# 2_MCU.net
KiCad netlist of a schematic drawn in Altium Designer
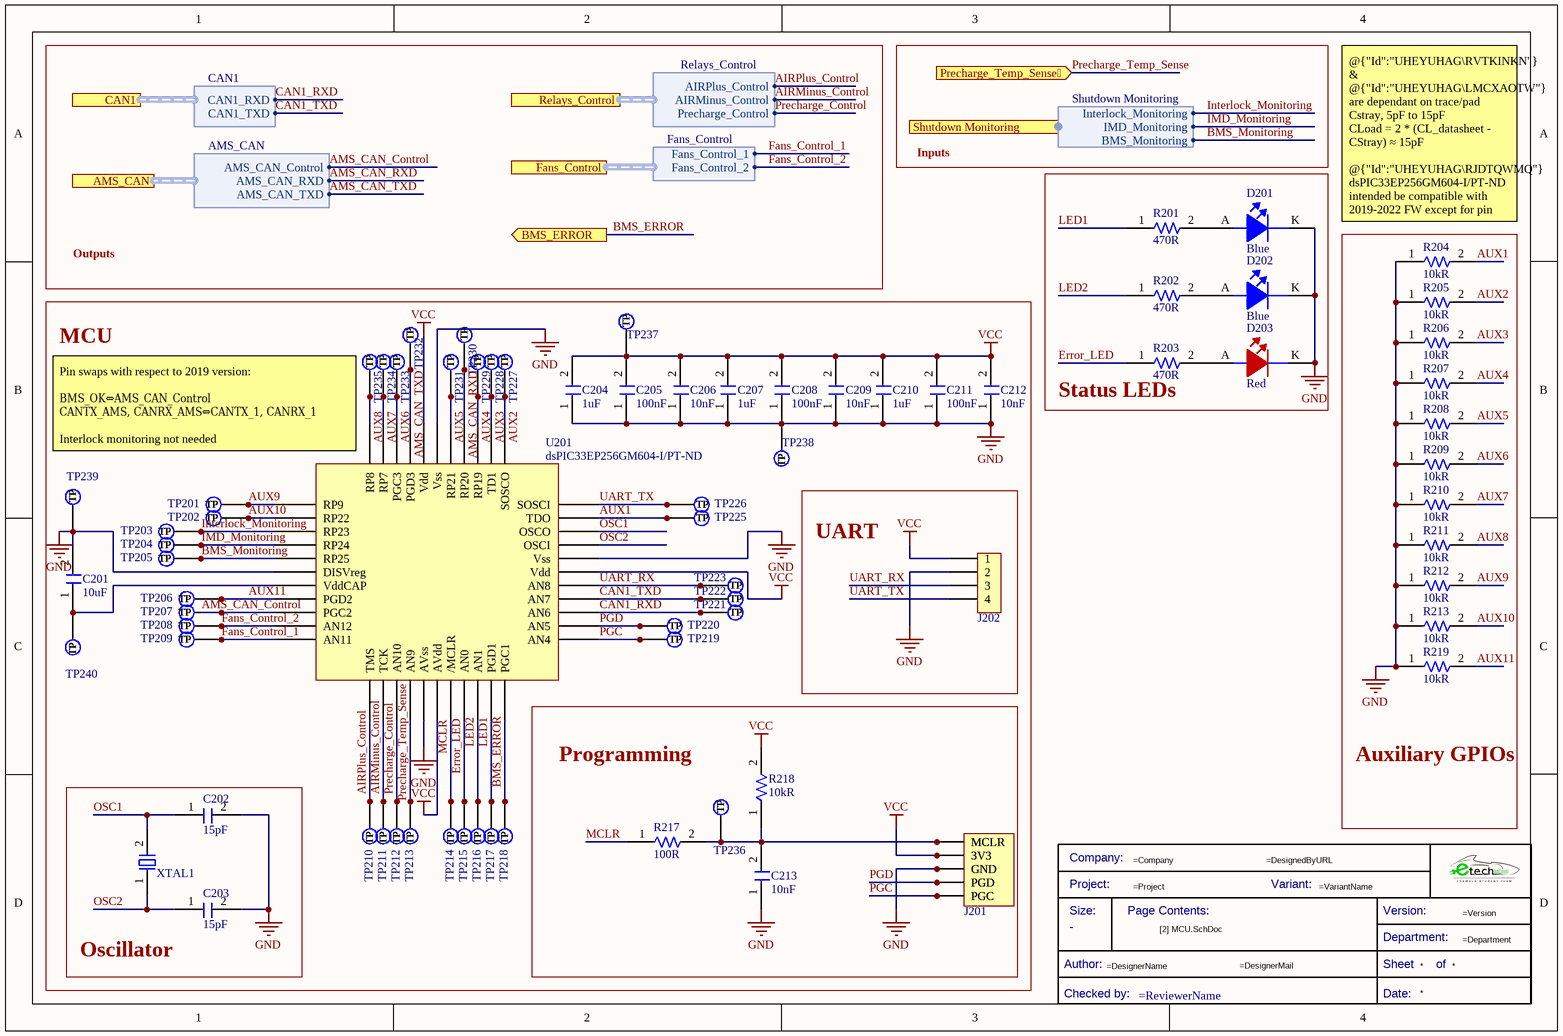
[diagram p0: [2] MCU.SchDoc]

(export (version "E")
  (design (tool "Eeschema 10.0.6"))
  (components
    (comp (ref "*")
      (value "Title Block_template")
      (description "Standard Title Block")
      (fields (field (name "SIZE") "-"))
      (libsource (lib "e-Tech_Racing") (part "Title Block_template"))
    )
    (comp (ref "C201")
      (value "885012208018")
      (footprint "C1206FNPC-RW")
      (description "Cap, 10ΜF, 10V, 10%, X7R, 1206")
      (fields
        (field (name "TOLERANCE") "10%")
        (field (name "CAPACITANCE") "10uF")
        (field (name ".CREATOR") "GP")
      )
      (libsource (lib "Passives") (part "C10u-10V-1206FNPC-X7R"))
    )
    (comp (ref "C202")
      (value "885012007052")
      (footprint "C0805FNPC-R")
      (description "Cap, 15PF, 50V, 5%, C0G/NP0, 0805")
      (fields
        (field (name "TOLERANCE") "5%")
        (field (name "CAPACITANCE") "15pF")
        (field (name ".CREATOR") "DR")
      )
      (libsource (lib "Passives") (part "C15p-50V-0805FNPC-NP0"))
    )
    (comp (ref "C203")
      (value "885012007052")
      (footprint "C0805FNPC-R")
      (description "Cap, 15PF, 50V, 5%, C0G/NP0, 0805")
      (fields
        (field (name "TOLERANCE") "5%")
        (field (name "CAPACITANCE") "15pF")
        (field (name ".CREATOR") "DR")
      )
      (libsource (lib "Passives") (part "C15p-50V-0805FNPC-NP0"))
    )
    (comp (ref "C204")
      (value "885012207103")
      (footprint "C0805FNPC-R")
      (fields
        (field (name "TOLERANCE") "10%")
        (field (name "CAPACITANCE") "1uF")
        (field (name ".CREATOR") "GP")
      )
      (libsource (lib "Passives") (part "C1u-50V-0805FNPC-X7R"))
    )
    (comp (ref "C205")
      (value "885012207098")
      (footprint "C0805FNPC-R")
      (description "Cap, 0.1ΜF, 50V, 10%, X7R, 0805")
      (fields
        (field (name "TOLERANCE") "10%")
        (field (name "CAPACITANCE") "100nF")
        (field (name ".CREATOR") "DR")
      )
      (libsource (lib "Passives") (part "C100n-50V-0805FNPC-X7R"))
    )
    (comp (ref "C206")
      (value "885012207092")
      (footprint "C0805FNPC-R")
      (description "Cap, 0.01ΜF, 50V, 10%, X7R, 0805")
      (fields
        (field (name "TOLERANCE") "10%")
        (field (name "CAPACITANCE") "10nF")
        (field (name ".CREATOR") "DR")
      )
      (libsource (lib "Passives") (part "C10n-50V-0805FNPC-X7R"))
    )
    (comp (ref "C207")
      (value "885012207103")
      (footprint "C0805FNPC-R")
      (fields
        (field (name "TOLERANCE") "10%")
        (field (name "CAPACITANCE") "1uF")
        (field (name ".CREATOR") "GP")
      )
      (libsource (lib "Passives") (part "C1u-50V-0805FNPC-X7R"))
    )
    (comp (ref "C208")
      (value "885012207098")
      (footprint "C0805FNPC-R")
      (description "Cap, 0.1ΜF, 50V, 10%, X7R, 0805")
      (fields
        (field (name "TOLERANCE") "10%")
        (field (name "CAPACITANCE") "100nF")
        (field (name ".CREATOR") "DR")
      )
      (libsource (lib "Passives") (part "C100n-50V-0805FNPC-X7R"))
    )
    (comp (ref "C209")
      (value "885012207092")
      (footprint "C0805FNPC-R")
      (description "Cap, 0.01ΜF, 50V, 10%, X7R, 0805")
      (fields
        (field (name "TOLERANCE") "10%")
        (field (name "CAPACITANCE") "10nF")
        (field (name ".CREATOR") "DR")
      )
      (libsource (lib "Passives") (part "C10n-50V-0805FNPC-X7R"))
    )
    (comp (ref "C210")
      (value "885012207103")
      (footprint "C0805FNPC-R")
      (fields
        (field (name "TOLERANCE") "10%")
        (field (name "CAPACITANCE") "1uF")
        (field (name ".CREATOR") "GP")
      )
      (libsource (lib "Passives") (part "C1u-50V-0805FNPC-X7R"))
    )
    (comp (ref "C211")
      (value "885012207098")
      (footprint "C0805FNPC-R")
      (description "Cap, 0.1ΜF, 50V, 10%, X7R, 0805")
      (fields
        (field (name "TOLERANCE") "10%")
        (field (name "CAPACITANCE") "100nF")
        (field (name ".CREATOR") "DR")
      )
      (libsource (lib "Passives") (part "C100n-50V-0805FNPC-X7R"))
    )
    (comp (ref "C212")
      (value "885012207092")
      (footprint "C0805FNPC-R")
      (description "Cap, 0.01ΜF, 50V, 10%, X7R, 0805")
      (fields
        (field (name "TOLERANCE") "10%")
        (field (name "CAPACITANCE") "10nF")
        (field (name ".CREATOR") "DR")
      )
      (libsource (lib "Passives") (part "C10n-50V-0805FNPC-X7R"))
    )
    (comp (ref "C213")
      (value "885012207092")
      (footprint "C0805FNPC-R")
      (description "Cap, 0.01ΜF, 50V, 10%, X7R, 0805")
      (fields
        (field (name "TOLERANCE") "10%")
        (field (name "CAPACITANCE") "10nF")
        (field (name ".CREATOR") "DR")
      )
      (libsource (lib "Passives") (part "C10n-50V-0805FNPC-X7R"))
    )
    (comp (ref "D201")
      (value "150080BS75000")
      (footprint "LED_0805_WE")
      (description "LED BLUE CLEAR 0805 SMD")
      (fields (field (name "COLOR") "Blue") (field (name ".CREATOR") "GP"))
      (libsource (lib "Semiconductor") (part "LEDBS-0805-145"))
    )
    (comp (ref "D202")
      (value "150080BS75000")
      (footprint "LED_0805_WE")
      (description "LED BLUE CLEAR 0805 SMD")
      (fields (field (name "COLOR") "Blue") (field (name ".CREATOR") "GP"))
      (libsource (lib "Semiconductor") (part "LEDBS-0805-145"))
    )
    (comp (ref "D203")
      (value "150080RS75000")
      (footprint "LED_0805_WE")
      (description "0805(H=0.8mm) 红色 高亮 λD=625nm VF=2V IF=30mA PD=72mW")
      (fields (field (name "COLOR") "Red") (field (name ".CREATOR") "DR"))
      (libsource (lib "Semiconductor") (part "LEDRS-0805-150"))
    )
    (comp (ref "J201")
      (value "61300511121")
      (footprint "J_PinHeader_1x5")
      (description "THT Vertical Pin Header WR-PHD, Pitch 2.54 mm, Single Row, 5 pins")
      (fields (field (name "MANUFACTURER") "Molex") (field (name ".CREATOR") "GP"))
      (libsource (lib "Electromechanical") (part "J_Pickit3"))
    )
    (comp (ref "J202")
      (value "61300411121")
      (footprint "J_PinHeader_1x4")
      (description "CONN HEADER 4 POS 2.54")
      (fields (field (name ".CREATOR") "AC"))
      (libsource (lib "Electromechanical") (part "J_UART"))
    )
    (comp (ref "R201")
      (value "CR0805-FX-4700GLF")
      (footprint "R0805FTK")
      (description "Res Thick Film 0805 470 Ohm 1% 1/8W ±100ppm/°C Molded SMD SMD Paper Tape on Plastic Reel")
      (fields
        (field (name "TOLERANCE") "1%")
        (field (name "RESISTANCE") "470R")
        (field (name ".CREATOR") "DR")
      )
      (libsource (lib "Passives") (part "R470-0805FTK"))
    )
    (comp (ref "R202")
      (value "CR0805-FX-4700GLF")
      (footprint "R0805FTK")
      (description "Res Thick Film 0805 470 Ohm 1% 1/8W ±100ppm/°C Molded SMD SMD Paper Tape on Plastic Reel")
      (fields
        (field (name "TOLERANCE") "1%")
        (field (name "RESISTANCE") "470R")
        (field (name ".CREATOR") "DR")
      )
      (libsource (lib "Passives") (part "R470-0805FTK"))
    )
    (comp (ref "R203")
      (value "CR0805-FX-4700GLF")
      (footprint "R0805FTK")
      (description "Res Thick Film 0805 470 Ohm 1% 1/8W ±100ppm/°C Molded SMD SMD Paper Tape on Plastic Reel")
      (fields
        (field (name "TOLERANCE") "1%")
        (field (name "RESISTANCE") "470R")
        (field (name ".CREATOR") "DR")
      )
      (libsource (lib "Passives") (part "R470-0805FTK"))
    )
    (comp (ref "R204")
      (value "CR0805-JW-103ELF")
      (footprint "R0805FTK")
      (fields
        (field (name "TOLERANCE") "5%")
        (field (name "RESISTANCE") "10kR")
        (field (name ".CREATOR") "DR")
      )
      (libsource (lib "Passives") (part "R10k-0805FTK"))
    )
    (comp (ref "R205")
      (value "CR0805-JW-103ELF")
      (footprint "R0805FTK")
      (fields
        (field (name "TOLERANCE") "5%")
        (field (name "RESISTANCE") "10kR")
        (field (name ".CREATOR") "DR")
      )
      (libsource (lib "Passives") (part "R10k-0805FTK"))
    )
    (comp (ref "R206")
      (value "CR0805-JW-103ELF")
      (footprint "R0805FTK")
      (fields
        (field (name "TOLERANCE") "5%")
        (field (name "RESISTANCE") "10kR")
        (field (name ".CREATOR") "DR")
      )
      (libsource (lib "Passives") (part "R10k-0805FTK"))
    )
    (comp (ref "R207")
      (value "CR0805-JW-103ELF")
      (footprint "R0805FTK")
      (fields
        (field (name "TOLERANCE") "5%")
        (field (name "RESISTANCE") "10kR")
        (field (name ".CREATOR") "DR")
      )
      (libsource (lib "Passives") (part "R10k-0805FTK"))
    )
    (comp (ref "R208")
      (value "CR0805-JW-103ELF")
      (footprint "R0805FTK")
      (fields
        (field (name "TOLERANCE") "5%")
        (field (name "RESISTANCE") "10kR")
        (field (name ".CREATOR") "DR")
      )
      (libsource (lib "Passives") (part "R10k-0805FTK"))
    )
    (comp (ref "R209")
      (value "CR0805-JW-103ELF")
      (footprint "R0805FTK")
      (fields
        (field (name "TOLERANCE") "5%")
        (field (name "RESISTANCE") "10kR")
        (field (name ".CREATOR") "DR")
      )
      (libsource (lib "Passives") (part "R10k-0805FTK"))
    )
    (comp (ref "R210")
      (value "CR0805-JW-103ELF")
      (footprint "R0805FTK")
      (fields
        (field (name "TOLERANCE") "5%")
        (field (name "RESISTANCE") "10kR")
        (field (name ".CREATOR") "DR")
      )
      (libsource (lib "Passives") (part "R10k-0805FTK"))
    )
    (comp (ref "R211")
      (value "CR0805-JW-103ELF")
      (footprint "R0805FTK")
      (fields
        (field (name "TOLERANCE") "5%")
        (field (name "RESISTANCE") "10kR")
        (field (name ".CREATOR") "DR")
      )
      (libsource (lib "Passives") (part "R10k-0805FTK"))
    )
    (comp (ref "R212")
      (value "CR0805-JW-103ELF")
      (footprint "R0805FTK")
      (fields
        (field (name "TOLERANCE") "5%")
        (field (name "RESISTANCE") "10kR")
        (field (name ".CREATOR") "DR")
      )
      (libsource (lib "Passives") (part "R10k-0805FTK"))
    )
    (comp (ref "R213")
      (value "CR0805-JW-103ELF")
      (footprint "R0805FTK")
      (fields
        (field (name "TOLERANCE") "5%")
        (field (name "RESISTANCE") "10kR")
        (field (name ".CREATOR") "DR")
      )
      (libsource (lib "Passives") (part "R10k-0805FTK"))
    )
    (comp (ref "R217")
      (value "CR0805-FX-1000ELF")
      (footprint "R0805FTK")
      (description "Res Thick Film 0805 100 Ohm 1% 1/8W ±100ppm/°C Molded SMD SMD Paper Tape on Plastic Reel")
      (fields
        (field (name "TOLERANCE") "1%")
        (field (name "RESISTANCE") "100R")
        (field (name ".CREATOR") "DR")
      )
      (libsource (lib "Passives") (part "R100-0805FTK"))
    )
    (comp (ref "R218")
      (value "CR0805-JW-103ELF")
      (footprint "R0805FTK")
      (fields
        (field (name "TOLERANCE") "5%")
        (field (name "RESISTANCE") "10kR")
        (field (name ".CREATOR") "DR")
      )
      (libsource (lib "Passives") (part "R10k-0805FTK"))
    )
    (comp (ref "R219")
      (value "CR0805-JW-103ELF")
      (footprint "R0805FTK")
      (fields
        (field (name "TOLERANCE") "5%")
        (field (name "RESISTANCE") "10kR")
        (field (name ".CREATOR") "DR")
      )
      (libsource (lib "Passives") (part "R10k-0805FTK"))
    )
    (comp (ref "TP201")
      (value "TestPoint")
      (footprint "TestPoint")
      (description "Test Point 1x1 mm")
      (fields (field (name ".CREATOR") "GP") (field (name ".PCBCHECK") "GP") (field (name ".SCHCHECK") "GP"))
      (libsource (lib "e-Tech_Racing") (part "TestPoint"))
    )
    (comp (ref "TP202")
      (value "TestPoint")
      (footprint "TestPoint")
      (description "Test Point 1x1 mm")
      (fields (field (name ".CREATOR") "GP") (field (name ".PCBCHECK") "GP") (field (name ".SCHCHECK") "GP"))
      (libsource (lib "e-Tech_Racing") (part "TestPoint"))
    )
    (comp (ref "TP203")
      (value "TestPoint")
      (footprint "TestPoint")
      (description "Test Point 1x1 mm")
      (fields (field (name ".CREATOR") "GP") (field (name ".PCBCHECK") "GP") (field (name ".SCHCHECK") "GP"))
      (libsource (lib "e-Tech_Racing") (part "TestPoint"))
    )
    (comp (ref "TP204")
      (value "TestPoint")
      (footprint "TestPoint")
      (description "Test Point 1x1 mm")
      (fields (field (name ".CREATOR") "GP") (field (name ".PCBCHECK") "GP") (field (name ".SCHCHECK") "GP"))
      (libsource (lib "e-Tech_Racing") (part "TestPoint"))
    )
    (comp (ref "TP205")
      (value "TestPoint")
      (footprint "TestPoint")
      (description "Test Point 1x1 mm")
      (fields (field (name ".CREATOR") "GP") (field (name ".PCBCHECK") "GP") (field (name ".SCHCHECK") "GP"))
      (libsource (lib "e-Tech_Racing") (part "TestPoint"))
    )
    (comp (ref "TP206")
      (value "TestPoint")
      (footprint "TestPoint")
      (description "Test Point 1x1 mm")
      (fields (field (name ".CREATOR") "GP") (field (name ".PCBCHECK") "GP") (field (name ".SCHCHECK") "GP"))
      (libsource (lib "e-Tech_Racing") (part "TestPoint"))
    )
    (comp (ref "TP207")
      (value "TestPoint")
      (footprint "TestPoint")
      (description "Test Point 1x1 mm")
      (fields (field (name ".CREATOR") "GP") (field (name ".PCBCHECK") "GP") (field (name ".SCHCHECK") "GP"))
      (libsource (lib "e-Tech_Racing") (part "TestPoint"))
    )
    (comp (ref "TP208")
      (value "TestPoint")
      (footprint "TestPoint")
      (description "Test Point 1x1 mm")
      (fields (field (name ".CREATOR") "GP") (field (name ".PCBCHECK") "GP") (field (name ".SCHCHECK") "GP"))
      (libsource (lib "e-Tech_Racing") (part "TestPoint"))
    )
    (comp (ref "TP209")
      (value "TestPoint")
      (footprint "TestPoint")
      (description "Test Point 1x1 mm")
      (fields (field (name ".CREATOR") "GP") (field (name ".PCBCHECK") "GP") (field (name ".SCHCHECK") "GP"))
      (libsource (lib "e-Tech_Racing") (part "TestPoint"))
    )
    (comp (ref "TP210")
      (value "TestPoint")
      (footprint "TestPoint")
      (description "Test Point 1x1 mm")
      (fields (field (name ".CREATOR") "GP") (field (name ".PCBCHECK") "GP") (field (name ".SCHCHECK") "GP"))
      (libsource (lib "e-Tech_Racing") (part "TestPoint"))
    )
    (comp (ref "TP211")
      (value "TestPoint")
      (footprint "TestPoint")
      (description "Test Point 1x1 mm")
      (fields (field (name ".CREATOR") "GP") (field (name ".PCBCHECK") "GP") (field (name ".SCHCHECK") "GP"))
      (libsource (lib "e-Tech_Racing") (part "TestPoint"))
    )
    (comp (ref "TP212")
      (value "TestPoint")
      (footprint "TestPoint")
      (description "Test Point 1x1 mm")
      (fields (field (name ".CREATOR") "GP") (field (name ".PCBCHECK") "GP") (field (name ".SCHCHECK") "GP"))
      (libsource (lib "e-Tech_Racing") (part "TestPoint"))
    )
    (comp (ref "TP213")
      (value "TestPoint")
      (footprint "TestPoint")
      (description "Test Point 1x1 mm")
      (fields (field (name ".CREATOR") "GP") (field (name ".PCBCHECK") "GP") (field (name ".SCHCHECK") "GP"))
      (libsource (lib "e-Tech_Racing") (part "TestPoint"))
    )
    (comp (ref "TP214")
      (value "TestPoint")
      (footprint "TestPoint")
      (description "Test Point 1x1 mm")
      (fields (field (name ".CREATOR") "GP") (field (name ".PCBCHECK") "GP") (field (name ".SCHCHECK") "GP"))
      (libsource (lib "e-Tech_Racing") (part "TestPoint"))
    )
    (comp (ref "TP215")
      (value "TestPoint")
      (footprint "TestPoint")
      (description "Test Point 1x1 mm")
      (fields (field (name ".CREATOR") "GP") (field (name ".PCBCHECK") "GP") (field (name ".SCHCHECK") "GP"))
      (libsource (lib "e-Tech_Racing") (part "TestPoint"))
    )
    (comp (ref "TP216")
      (value "TestPoint")
      (footprint "TestPoint")
      (description "Test Point 1x1 mm")
      (fields (field (name ".CREATOR") "GP") (field (name ".PCBCHECK") "GP") (field (name ".SCHCHECK") "GP"))
      (libsource (lib "e-Tech_Racing") (part "TestPoint"))
    )
    (comp (ref "TP217")
      (value "TestPoint")
      (footprint "TestPoint")
      (description "Test Point 1x1 mm")
      (fields (field (name ".CREATOR") "GP") (field (name ".PCBCHECK") "GP") (field (name ".SCHCHECK") "GP"))
      (libsource (lib "e-Tech_Racing") (part "TestPoint"))
    )
    (comp (ref "TP218")
      (value "TestPoint")
      (footprint "TestPoint")
      (description "Test Point 1x1 mm")
      (fields (field (name ".CREATOR") "GP") (field (name ".PCBCHECK") "GP") (field (name ".SCHCHECK") "GP"))
      (libsource (lib "e-Tech_Racing") (part "TestPoint"))
    )
    (comp (ref "TP219")
      (value "TestPoint")
      (footprint "TestPoint")
      (description "Test Point 1x1 mm")
      (fields (field (name ".CREATOR") "GP") (field (name ".PCBCHECK") "GP") (field (name ".SCHCHECK") "GP"))
      (libsource (lib "e-Tech_Racing") (part "TestPoint"))
    )
    (comp (ref "TP220")
      (value "TestPoint")
      (footprint "TestPoint")
      (description "Test Point 1x1 mm")
      (fields (field (name ".CREATOR") "GP") (field (name ".PCBCHECK") "GP") (field (name ".SCHCHECK") "GP"))
      (libsource (lib "e-Tech_Racing") (part "TestPoint"))
    )
    (comp (ref "TP221")
      (value "TestPoint")
      (footprint "TestPoint")
      (description "Test Point 1x1 mm")
      (fields (field (name ".CREATOR") "GP") (field (name ".PCBCHECK") "GP") (field (name ".SCHCHECK") "GP"))
      (libsource (lib "e-Tech_Racing") (part "TestPoint"))
    )
    (comp (ref "TP222")
      (value "TestPoint")
      (footprint "TestPoint")
      (description "Test Point 1x1 mm")
      (fields (field (name ".CREATOR") "GP") (field (name ".PCBCHECK") "GP") (field (name ".SCHCHECK") "GP"))
      (libsource (lib "e-Tech_Racing") (part "TestPoint"))
    )
    (comp (ref "TP223")
      (value "TestPoint")
      (footprint "TestPoint")
      (description "Test Point 1x1 mm")
      (fields (field (name ".CREATOR") "GP") (field (name ".PCBCHECK") "GP") (field (name ".SCHCHECK") "GP"))
      (libsource (lib "e-Tech_Racing") (part "TestPoint"))
    )
    (comp (ref "TP225")
      (value "TestPoint")
      (footprint "TestPoint")
      (description "Test Point 1x1 mm")
      (fields (field (name ".CREATOR") "GP") (field (name ".PCBCHECK") "GP") (field (name ".SCHCHECK") "GP"))
      (libsource (lib "e-Tech_Racing") (part "TestPoint"))
    )
    (comp (ref "TP226")
      (value "TestPoint")
      (footprint "TestPoint")
      (description "Test Point 1x1 mm")
      (fields (field (name ".CREATOR") "GP") (field (name ".PCBCHECK") "GP") (field (name ".SCHCHECK") "GP"))
      (libsource (lib "e-Tech_Racing") (part "TestPoint"))
    )
    (comp (ref "TP227")
      (value "TestPoint")
      (footprint "TestPoint")
      (description "Test Point 1x1 mm")
      (fields (field (name ".CREATOR") "GP") (field (name ".PCBCHECK") "GP") (field (name ".SCHCHECK") "GP"))
      (libsource (lib "e-Tech_Racing") (part "TestPoint"))
    )
    (comp (ref "TP228")
      (value "TestPoint")
      (footprint "TestPoint")
      (description "Test Point 1x1 mm")
      (fields (field (name ".CREATOR") "GP") (field (name ".PCBCHECK") "GP") (field (name ".SCHCHECK") "GP"))
      (libsource (lib "e-Tech_Racing") (part "TestPoint"))
    )
    (comp (ref "TP229")
      (value "TestPoint")
      (footprint "TestPoint")
      (description "Test Point 1x1 mm")
      (fields (field (name ".CREATOR") "GP") (field (name ".PCBCHECK") "GP") (field (name ".SCHCHECK") "GP"))
      (libsource (lib "e-Tech_Racing") (part "TestPoint"))
    )
    (comp (ref "TP230")
      (value "TestPoint")
      (footprint "TestPoint")
      (description "Test Point 1x1 mm")
      (fields (field (name ".CREATOR") "GP") (field (name ".PCBCHECK") "GP") (field (name ".SCHCHECK") "GP"))
      (libsource (lib "e-Tech_Racing") (part "TestPoint"))
    )
    (comp (ref "TP231")
      (value "TestPoint")
      (footprint "TestPoint")
      (description "Test Point 1x1 mm")
      (fields (field (name ".CREATOR") "GP") (field (name ".PCBCHECK") "GP") (field (name ".SCHCHECK") "GP"))
      (libsource (lib "e-Tech_Racing") (part "TestPoint"))
    )
    (comp (ref "TP232")
      (value "TestPoint")
      (footprint "TestPoint")
      (description "Test Point 1x1 mm")
      (fields (field (name ".CREATOR") "GP") (field (name ".PCBCHECK") "GP") (field (name ".SCHCHECK") "GP"))
      (libsource (lib "e-Tech_Racing") (part "TestPoint"))
    )
    (comp (ref "TP233")
      (value "TestPoint")
      (footprint "TestPoint")
      (description "Test Point 1x1 mm")
      (fields (field (name ".CREATOR") "GP") (field (name ".PCBCHECK") "GP") (field (name ".SCHCHECK") "GP"))
      (libsource (lib "e-Tech_Racing") (part "TestPoint"))
    )
    (comp (ref "TP234")
      (value "TestPoint")
      (footprint "TestPoint")
      (description "Test Point 1x1 mm")
      (fields (field (name ".CREATOR") "GP") (field (name ".PCBCHECK") "GP") (field (name ".SCHCHECK") "GP"))
      (libsource (lib "e-Tech_Racing") (part "TestPoint"))
    )
    (comp (ref "TP235")
      (value "TestPoint")
      (footprint "TestPoint")
      (description "Test Point 1x1 mm")
      (fields (field (name ".CREATOR") "GP") (field (name ".PCBCHECK") "GP") (field (name ".SCHCHECK") "GP"))
      (libsource (lib "e-Tech_Racing") (part "TestPoint"))
    )
    (comp (ref "TP236")
      (value "TestPoint")
      (footprint "TestPoint")
      (description "Test Point 1x1 mm")
      (fields (field (name ".CREATOR") "GP") (field (name ".PCBCHECK") "GP") (field (name ".SCHCHECK") "GP"))
      (libsource (lib "e-Tech_Racing") (part "TestPoint"))
    )
    (comp (ref "TP237")
      (value "TestPoint")
      (footprint "TestPoint")
      (description "Test Point 1x1 mm")
      (fields (field (name ".CREATOR") "GP") (field (name ".PCBCHECK") "GP") (field (name ".SCHCHECK") "GP"))
      (libsource (lib "e-Tech_Racing") (part "TestPoint"))
    )
    (comp (ref "TP238")
      (value "TestPoint")
      (footprint "TestPoint")
      (description "Test Point 1x1 mm")
      (fields (field (name ".CREATOR") "GP") (field (name ".PCBCHECK") "GP") (field (name ".SCHCHECK") "GP"))
      (libsource (lib "e-Tech_Racing") (part "TestPoint"))
    )
    (comp (ref "TP239")
      (value "TestPoint")
      (footprint "TestPoint")
      (description "Test Point 1x1 mm")
      (fields (field (name ".CREATOR") "GP") (field (name ".PCBCHECK") "GP") (field (name ".SCHCHECK") "GP"))
      (libsource (lib "e-Tech_Racing") (part "TestPoint"))
    )
    (comp (ref "TP240")
      (value "TestPoint")
      (footprint "TestPoint")
      (description "Test Point 1x1 mm")
      (fields (field (name ".CREATOR") "GP") (field (name ".PCBCHECK") "GP") (field (name ".SCHCHECK") "GP"))
      (libsource (lib "e-Tech_Racing") (part "TestPoint"))
    )
    (comp (ref "U201")
      (value "dsPIC33EP256GM604-I/PT")
      (footprint "U_dsPIC33EP256GM604-I/PT")
      (description "16-bit MCU/DSC, 256 KB, 32768 Bytes, 70 MHz, 3 to 3.6V, TQFP-44, RoHS")
      (fields
        (field (name "SUPPLIER PART NUMBER 1") "dsPIC33EP256GM604-I/PT-ND")
        (field (name ".CREATOR") "DR")
      )
      (libsource (lib "Integrated circuits") (part "U_dsPIC33EP256GM604-I/PT"))
    )
    (comp (ref "XTAL1")
      (value "830028710")
      (footprint "XTAL20M_SMD")
      (description "830028710, 20 MHz")
      (fields (field (name "MANUFACTURER") "Würth Elektronik") (field (name ".CREATOR") "GP"))
      (libsource (lib "Passives") (part "XTAL20M_SMD"))
    )
  )
  (nets
    (net (code "7") (name "/AIRMinus_Control") (class "Default")
      (node (ref "TP211") (pin "1") (pinfunction "TP_1") (pintype "passive"))
      (node (ref "U201") (pin "13") (pinfunction "TCK_13") (pintype "passive"))
    )
    (net (code "8") (name "/AIRPlus_Control") (class "Default")
      (node (ref "TP210") (pin "1") (pinfunction "TP_1") (pintype "passive"))
      (node (ref "U201") (pin "12") (pinfunction "TMS_12") (pintype "passive"))
    )
    (net (code "9") (name "/AMS_CAN_Control") (class "Default")
      (node (ref "TP207") (pin "1") (pinfunction "TP_1") (pintype "passive"))
      (node (ref "U201") (pin "9") (pinfunction "PGC2_9") (pintype "passive"))
    )
    (net (code "10") (name "/AMS_CAN_RXD") (class "Default")
      (node (ref "TP230") (pin "1") (pinfunction "TP_1") (pintype "passive"))
      (node (ref "U201") (pin "37") (pinfunction "RP20_37") (pintype "passive"))
    )
    (net (code "11") (name "/AMS_CAN_TXD") (class "Default")
      (node (ref "TP232") (pin "1") (pinfunction "TP_1") (pintype "passive"))
      (node (ref "U201") (pin "41") (pinfunction "PGD3_41") (pintype "passive"))
    )
    (net (code "12") (name "/AUX1") (class "Default")
      (node (ref "R204") (pin "2") (pinfunction "2_2") (pintype "passive"))
      (node (ref "TP225") (pin "1") (pinfunction "TP_1") (pintype "passive"))
      (node (ref "U201") (pin "32") (pinfunction "TDO_32") (pintype "passive"))
    )
    (net (code "13") (name "/AUX2") (class "Default")
      (node (ref "R205") (pin "2") (pinfunction "2_2") (pintype "passive"))
      (node (ref "TP227") (pin "1") (pinfunction "TP_1") (pintype "passive"))
      (node (ref "U201") (pin "34") (pinfunction "SOSCO_34") (pintype "passive"))
    )
    (net (code "14") (name "/AUX3") (class "Default")
      (node (ref "R206") (pin "2") (pinfunction "2_2") (pintype "passive"))
      (node (ref "TP228") (pin "1") (pinfunction "TP_1") (pintype "passive"))
      (node (ref "U201") (pin "35") (pinfunction "TD1_35") (pintype "passive"))
    )
    (net (code "15") (name "/AUX4") (class "Default")
      (node (ref "R207") (pin "2") (pinfunction "2_2") (pintype "passive"))
      (node (ref "TP229") (pin "1") (pinfunction "TP_1") (pintype "passive"))
      (node (ref "U201") (pin "36") (pinfunction "RP19_36") (pintype "passive"))
    )
    (net (code "16") (name "/AUX5") (class "Default")
      (node (ref "R208") (pin "2") (pinfunction "2_2") (pintype "passive"))
      (node (ref "TP231") (pin "1") (pinfunction "TP_1") (pintype "passive"))
      (node (ref "U201") (pin "38") (pinfunction "RP21_38") (pintype "passive"))
    )
    (net (code "17") (name "/AUX6") (class "Default")
      (node (ref "R209") (pin "2") (pinfunction "2_2") (pintype "passive"))
      (node (ref "TP233") (pin "1") (pinfunction "TP_1") (pintype "passive"))
      (node (ref "U201") (pin "42") (pinfunction "PGC3_42") (pintype "passive"))
    )
    (net (code "18") (name "/AUX7") (class "Default")
      (node (ref "R210") (pin "2") (pinfunction "2_2") (pintype "passive"))
      (node (ref "TP234") (pin "1") (pinfunction "TP_1") (pintype "passive"))
      (node (ref "U201") (pin "43") (pinfunction "RP7_43") (pintype "passive"))
    )
    (net (code "19") (name "/AUX8") (class "Default")
      (node (ref "R211") (pin "2") (pinfunction "2_2") (pintype "passive"))
      (node (ref "TP235") (pin "1") (pinfunction "TP_1") (pintype "passive"))
      (node (ref "U201") (pin "44") (pinfunction "RP8_44") (pintype "passive"))
    )
    (net (code "20") (name "/AUX9") (class "Default")
      (node (ref "R212") (pin "2") (pinfunction "2_2") (pintype "passive"))
      (node (ref "TP201") (pin "1") (pinfunction "TP_1") (pintype "passive"))
      (node (ref "U201") (pin "1") (pinfunction "RP9_1") (pintype "passive"))
    )
    (net (code "21") (name "/AUX10") (class "Default")
      (node (ref "R213") (pin "2") (pinfunction "2_2") (pintype "passive"))
      (node (ref "TP202") (pin "1") (pinfunction "TP_1") (pintype "passive"))
      (node (ref "U201") (pin "2") (pinfunction "RP22_2") (pintype "passive"))
    )
    (net (code "22") (name "/AUX11") (class "Default")
      (node (ref "R219") (pin "2") (pinfunction "2_2") (pintype "passive"))
      (node (ref "TP206") (pin "1") (pinfunction "TP_1") (pintype "passive"))
      (node (ref "U201") (pin "8") (pinfunction "PGD2_8") (pintype "passive"))
    )
    (net (code "23") (name "/BMS_ERROR") (class "Default")
      (node (ref "TP218") (pin "1") (pinfunction "TP_1") (pintype "passive"))
      (node (ref "U201") (pin "22") (pinfunction "PGC1_22") (pintype "passive"))
    )
    (net (code "24") (name "/BMS_Monitoring") (class "Default")
      (node (ref "TP205") (pin "1") (pinfunction "TP_1") (pintype "passive"))
      (node (ref "U201") (pin "5") (pinfunction "RP25_5") (pintype "passive"))
    )
    (net (code "25") (name "/CAN1_RXD") (class "Default")
      (node (ref "TP221") (pin "1") (pinfunction "TP_1") (pintype "passive"))
      (node (ref "U201") (pin "25") (pinfunction "AN6_25") (pintype "passive"))
    )
    (net (code "26") (name "/CAN1_TXD") (class "Default")
      (node (ref "TP222") (pin "1") (pinfunction "TP_1") (pintype "passive"))
      (node (ref "U201") (pin "26") (pinfunction "AN7_26") (pintype "passive"))
    )
    (net (code "27") (name "/Error_LED") (class "Default")
      (node (ref "R203") (pin "1") (pinfunction "1_1") (pintype "passive"))
      (node (ref "TP215") (pin "1") (pinfunction "TP_1") (pintype "passive"))
      (node (ref "U201") (pin "19") (pinfunction "AN0_19") (pintype "passive"))
    )
    (net (code "28") (name "/Fans_Control_1") (class "Default")
      (node (ref "TP209") (pin "1") (pinfunction "TP_1") (pintype "passive"))
      (node (ref "U201") (pin "11") (pinfunction "AN11_11") (pintype "passive"))
    )
    (net (code "29") (name "/Fans_Control_2") (class "Default")
      (node (ref "TP208") (pin "1") (pinfunction "TP_1") (pintype "passive"))
      (node (ref "U201") (pin "10") (pinfunction "AN12_10") (pintype "passive"))
    )
    (net (code "30") (name "/IMD_Monitoring") (class "Default")
      (node (ref "TP204") (pin "1") (pinfunction "TP_1") (pintype "passive"))
      (node (ref "U201") (pin "4") (pinfunction "RP24_4") (pintype "passive"))
    )
    (net (code "31") (name "/Interlock_Monitoring") (class "Default")
      (node (ref "TP203") (pin "1") (pinfunction "TP_1") (pintype "passive"))
      (node (ref "U201") (pin "3") (pinfunction "RP23_3") (pintype "passive"))
    )
    (net (code "32") (name "/LED1") (class "Default")
      (node (ref "R201") (pin "1") (pinfunction "1_1") (pintype "passive"))
      (node (ref "TP217") (pin "1") (pinfunction "TP_1") (pintype "passive"))
      (node (ref "U201") (pin "21") (pinfunction "PGD1_21") (pintype "passive"))
    )
    (net (code "33") (name "/LED2") (class "Default")
      (node (ref "R202") (pin "1") (pinfunction "1_1") (pintype "passive"))
      (node (ref "TP216") (pin "1") (pinfunction "TP_1") (pintype "passive"))
      (node (ref "U201") (pin "20") (pinfunction "AN1_20") (pintype "passive"))
    )
    (net (code "34") (name "/MCLR") (class "Default")
      (node (ref "R217") (pin "1") (pinfunction "1_1") (pintype "passive"))
      (node (ref "TP214") (pin "1") (pinfunction "TP_1") (pintype "passive"))
      (node (ref "U201") (pin "18") (pinfunction "/MCLR_18") (pintype "passive"))
    )
    (net (code "35") (name "/OSC1") (class "Default")
      (node (ref "C202") (pin "1") (pinfunction "1_1") (pintype "passive"))
      (node (ref "U201") (pin "31") (pinfunction "OSCO_31") (pintype "passive"))
      (node (ref "XTAL1") (pin "2") (pinfunction "2_2") (pintype "passive"))
    )
    (net (code "36") (name "/OSC2") (class "Default")
      (node (ref "C203") (pin "1") (pinfunction "1_1") (pintype "passive"))
      (node (ref "U201") (pin "30") (pinfunction "OSCI_30") (pintype "passive"))
      (node (ref "XTAL1") (pin "1") (pinfunction "1_1") (pintype "passive"))
    )
    (net (code "37") (name "/PGC") (class "Default")
      (node (ref "J201") (pin "5") (pinfunction "PGC_5") (pintype "passive"))
      (node (ref "TP219") (pin "1") (pinfunction "TP_1") (pintype "passive"))
      (node (ref "U201") (pin "23") (pinfunction "AN4_23") (pintype "passive"))
    )
    (net (code "38") (name "/PGD") (class "Default")
      (node (ref "J201") (pin "4") (pinfunction "PGD_4") (pintype "passive"))
      (node (ref "TP220") (pin "1") (pinfunction "TP_1") (pintype "passive"))
      (node (ref "U201") (pin "24") (pinfunction "AN5_24") (pintype "passive"))
    )
    (net (code "39") (name "/Precharge_Control") (class "Default")
      (node (ref "TP212") (pin "1") (pinfunction "TP_1") (pintype "passive"))
      (node (ref "U201") (pin "14") (pinfunction "AN10_14") (pintype "passive"))
    )
    (net (code "40") (name "/Precharge_Temp_Sense") (class "Default")
      (node (ref "TP213") (pin "1") (pinfunction "TP_1") (pintype "passive"))
      (node (ref "U201") (pin "15") (pinfunction "AN9_15") (pintype "passive"))
    )
    (net (code "41") (name "/UART_RX") (class "Default")
      (node (ref "J202") (pin "3") (pinfunction "3_3") (pintype "passive"))
      (node (ref "TP223") (pin "1") (pinfunction "TP_1") (pintype "passive"))
      (node (ref "U201") (pin "27") (pinfunction "AN8_27") (pintype "passive"))
    )
    (net (code "42") (name "/UART_TX") (class "Default")
      (node (ref "J202") (pin "4") (pinfunction "4_4") (pintype "passive"))
      (node (ref "TP226") (pin "1") (pinfunction "TP_1") (pintype "passive"))
      (node (ref "U201") (pin "33") (pinfunction "SOSCI_33") (pintype "passive"))
    )
    (net (code "48") (name "GND") (class "Default")
      (node (ref "C201") (pin "2") (pinfunction "2_2") (pintype "passive"))
      (node (ref "C202") (pin "2") (pinfunction "2_2") (pintype "passive"))
      (node (ref "C203") (pin "2") (pinfunction "2_2") (pintype "passive"))
      (node (ref "C204") (pin "1") (pinfunction "1_1") (pintype "passive"))
      (node (ref "C205") (pin "1") (pinfunction "1_1") (pintype "passive"))
      (node (ref "C206") (pin "1") (pinfunction "1_1") (pintype "passive"))
      (node (ref "C207") (pin "1") (pinfunction "1_1") (pintype "passive"))
      (node (ref "C208") (pin "1") (pinfunction "1_1") (pintype "passive"))
      (node (ref "C209") (pin "1") (pinfunction "1_1") (pintype "passive"))
      (node (ref "C210") (pin "1") (pinfunction "1_1") (pintype "passive"))
      (node (ref "C211") (pin "1") (pinfunction "1_1") (pintype "passive"))
      (node (ref "C212") (pin "1") (pinfunction "1_1") (pintype "passive"))
      (node (ref "C213") (pin "1") (pinfunction "1_1") (pintype "passive"))
      (node (ref "D201") (pin "K") (pinfunction "K_K") (pintype "passive"))
      (node (ref "D202") (pin "K") (pinfunction "K_K") (pintype "passive"))
      (node (ref "D203") (pin "K") (pinfunction "K_K") (pintype "passive"))
      (node (ref "J201") (pin "3") (pinfunction "GND_3") (pintype "passive"))
      (node (ref "J202") (pin "2") (pinfunction "2_2") (pintype "passive"))
      (node (ref "R204") (pin "1") (pinfunction "1_1") (pintype "passive"))
      (node (ref "R205") (pin "1") (pinfunction "1_1") (pintype "passive"))
      (node (ref "R206") (pin "1") (pinfunction "1_1") (pintype "passive"))
      (node (ref "R207") (pin "1") (pinfunction "1_1") (pintype "passive"))
      (node (ref "R208") (pin "1") (pinfunction "1_1") (pintype "passive"))
      (node (ref "R209") (pin "1") (pinfunction "1_1") (pintype "passive"))
      (node (ref "R210") (pin "1") (pinfunction "1_1") (pintype "passive"))
      (node (ref "R211") (pin "1") (pinfunction "1_1") (pintype "passive"))
      (node (ref "R212") (pin "1") (pinfunction "1_1") (pintype "passive"))
      (node (ref "R213") (pin "1") (pinfunction "1_1") (pintype "passive"))
      (node (ref "R219") (pin "1") (pinfunction "1_1") (pintype "passive"))
      (node (ref "TP238") (pin "1") (pinfunction "TP_1") (pintype "passive"))
      (node (ref "TP239") (pin "1") (pinfunction "TP_1") (pintype "passive"))
      (node (ref "U201") (pin "16") (pinfunction "AVss_16") (pintype "passive"))
      (node (ref "U201") (pin "29") (pinfunction "Vss_29") (pintype "passive"))
      (node (ref "U201") (pin "39") (pinfunction "Vss_39") (pintype "passive"))
      (node (ref "U201") (pin "6") (pinfunction "DISVreg_6") (pintype "passive"))
    )
    (net (code "49") (name "Net-(D201-PadA)") (class "Default")
      (node (ref "D201") (pin "A") (pinfunction "A_A") (pintype "passive"))
      (node (ref "R201") (pin "2") (pinfunction "2_2") (pintype "passive"))
    )
    (net (code "50") (name "Net-(D202-PadA)") (class "Default")
      (node (ref "D202") (pin "A") (pinfunction "A_A") (pintype "passive"))
      (node (ref "R202") (pin "2") (pinfunction "2_2") (pintype "passive"))
    )
    (net (code "51") (name "Net-(D203-PadA)") (class "Default")
      (node (ref "D203") (pin "A") (pinfunction "A_A") (pintype "passive"))
      (node (ref "R203") (pin "2") (pinfunction "2_2") (pintype "passive"))
    )
    (net (code "52") (name "Net-(J201-MCLR)") (class "Default")
      (node (ref "C213") (pin "2") (pinfunction "2_2") (pintype "passive"))
      (node (ref "J201") (pin "1") (pinfunction "MCLR_1") (pintype "passive"))
      (node (ref "R217") (pin "2") (pinfunction "2_2") (pintype "passive"))
      (node (ref "R218") (pin "1") (pinfunction "1_1") (pintype "passive"))
      (node (ref "TP236") (pin "1") (pinfunction "TP_1") (pintype "passive"))
    )
    (net (code "53") (name "Net-(TP240-TP)") (class "Default")
      (node (ref "C201") (pin "1") (pinfunction "1_1") (pintype "passive"))
      (node (ref "TP240") (pin "1") (pinfunction "TP_1") (pintype "passive"))
      (node (ref "U201") (pin "7") (pinfunction "VddCAP_7") (pintype "passive"))
    )
    (net (code "54") (name "VCC") (class "Default")
      (node (ref "C204") (pin "2") (pinfunction "2_2") (pintype "passive"))
      (node (ref "C205") (pin "2") (pinfunction "2_2") (pintype "passive"))
      (node (ref "C206") (pin "2") (pinfunction "2_2") (pintype "passive"))
      (node (ref "C207") (pin "2") (pinfunction "2_2") (pintype "passive"))
      (node (ref "C208") (pin "2") (pinfunction "2_2") (pintype "passive"))
      (node (ref "C209") (pin "2") (pinfunction "2_2") (pintype "passive"))
      (node (ref "C210") (pin "2") (pinfunction "2_2") (pintype "passive"))
      (node (ref "C211") (pin "2") (pinfunction "2_2") (pintype "passive"))
      (node (ref "C212") (pin "2") (pinfunction "2_2") (pintype "passive"))
      (node (ref "J201") (pin "2") (pinfunction "3V3_2") (pintype "passive"))
      (node (ref "J202") (pin "1") (pinfunction "1_1") (pintype "passive"))
      (node (ref "R218") (pin "2") (pinfunction "2_2") (pintype "passive"))
      (node (ref "TP237") (pin "1") (pinfunction "TP_1") (pintype "passive"))
      (node (ref "U201") (pin "17") (pinfunction "AVdd_17") (pintype "passive"))
      (node (ref "U201") (pin "28") (pinfunction "Vdd_28") (pintype "passive"))
      (node (ref "U201") (pin "40") (pinfunction "Vdd_40") (pintype "passive"))
    )
  )
)
